# Regulador5V.net
KiCad netlist of a schematic drawn in EAGLE
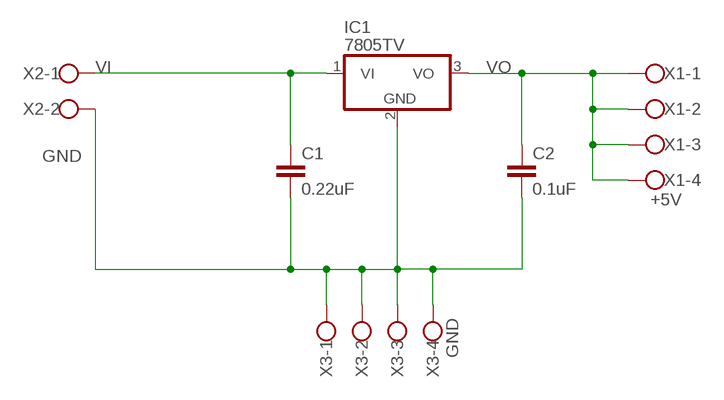
[diagram p0: schematic, sheet 1]

(export (version "E")
  (design (tool "Eeschema 10.0.6"))
  (components
    (comp (ref "C1")
      (value "0.22uF")
      (footprint "eagle-import:C2.5-2")
      (libsource (lib "eagle-import") (part "C2.5/2"))
    )
    (comp (ref "C2")
      (value "0.1uF")
      (footprint "eagle-import:C2.5-2")
      (libsource (lib "eagle-import") (part "C2.5/2"))
    )
    (comp (ref "IC1")
      (value "7805TV")
      (footprint "eagle-import:TO220V")
      (libsource (lib "eagle-import") (part "78TV05"))
    )
    (comp (ref "X1")
      (value "+5V")
      (footprint "eagle-import:W237-4")
      (libsource (lib "eagle-import") (part "W237-4"))
    )
    (comp (ref "X2")
      (value "W237-102")
      (footprint "eagle-import:W237-102")
      (fields (field (name "MPN") "237-102"))
      (libsource (lib "eagle-import") (part "W237-102"))
    )
    (comp (ref "X3")
      (value "GND")
      (footprint "eagle-import:W237-4")
      (libsource (lib "eagle-import") (part "W237-4"))
    )
  )
  (nets
    (net (code "1") (name "/GND") (class "Default")
      (node (ref "C1") (pin "2") (pinfunction "2_2") (pintype "passive"))
      (node (ref "C2") (pin "2") (pinfunction "2_2") (pintype "passive"))
      (node (ref "IC1") (pin "2") (pinfunction "GND_2") (pintype "passive"))
      (node (ref "X2") (pin "2") (pinfunction "KL_2") (pintype "passive"))
      (node (ref "X3") (pin "1") (pinfunction "KL_1") (pintype "passive"))
      (node (ref "X3") (pin "2") (pinfunction "KL_2") (pintype "passive"))
      (node (ref "X3") (pin "3") (pinfunction "KL_3") (pintype "passive"))
      (node (ref "X3") (pin "4") (pinfunction "KL_4") (pintype "passive"))
    )
    (net (code "2") (name "/VI") (class "Default")
      (node (ref "C1") (pin "1") (pinfunction "1_1") (pintype "passive"))
      (node (ref "IC1") (pin "1") (pinfunction "VI_1") (pintype "input"))
      (node (ref "X2") (pin "1") (pinfunction "KL_1") (pintype "passive"))
    )
    (net (code "3") (name "/VO") (class "Default")
      (node (ref "C2") (pin "1") (pinfunction "1_1") (pintype "passive"))
      (node (ref "IC1") (pin "3") (pinfunction "VO_3") (pintype "passive"))
      (node (ref "X1") (pin "1") (pinfunction "KL_1") (pintype "passive"))
      (node (ref "X1") (pin "2") (pinfunction "KL_2") (pintype "passive"))
      (node (ref "X1") (pin "3") (pinfunction "KL_3") (pintype "passive"))
      (node (ref "X1") (pin "4") (pinfunction "KL_4") (pintype "passive"))
    )
  )
)
